# HW2.net
KiCad netlist of a schematic drawn in EAGLE
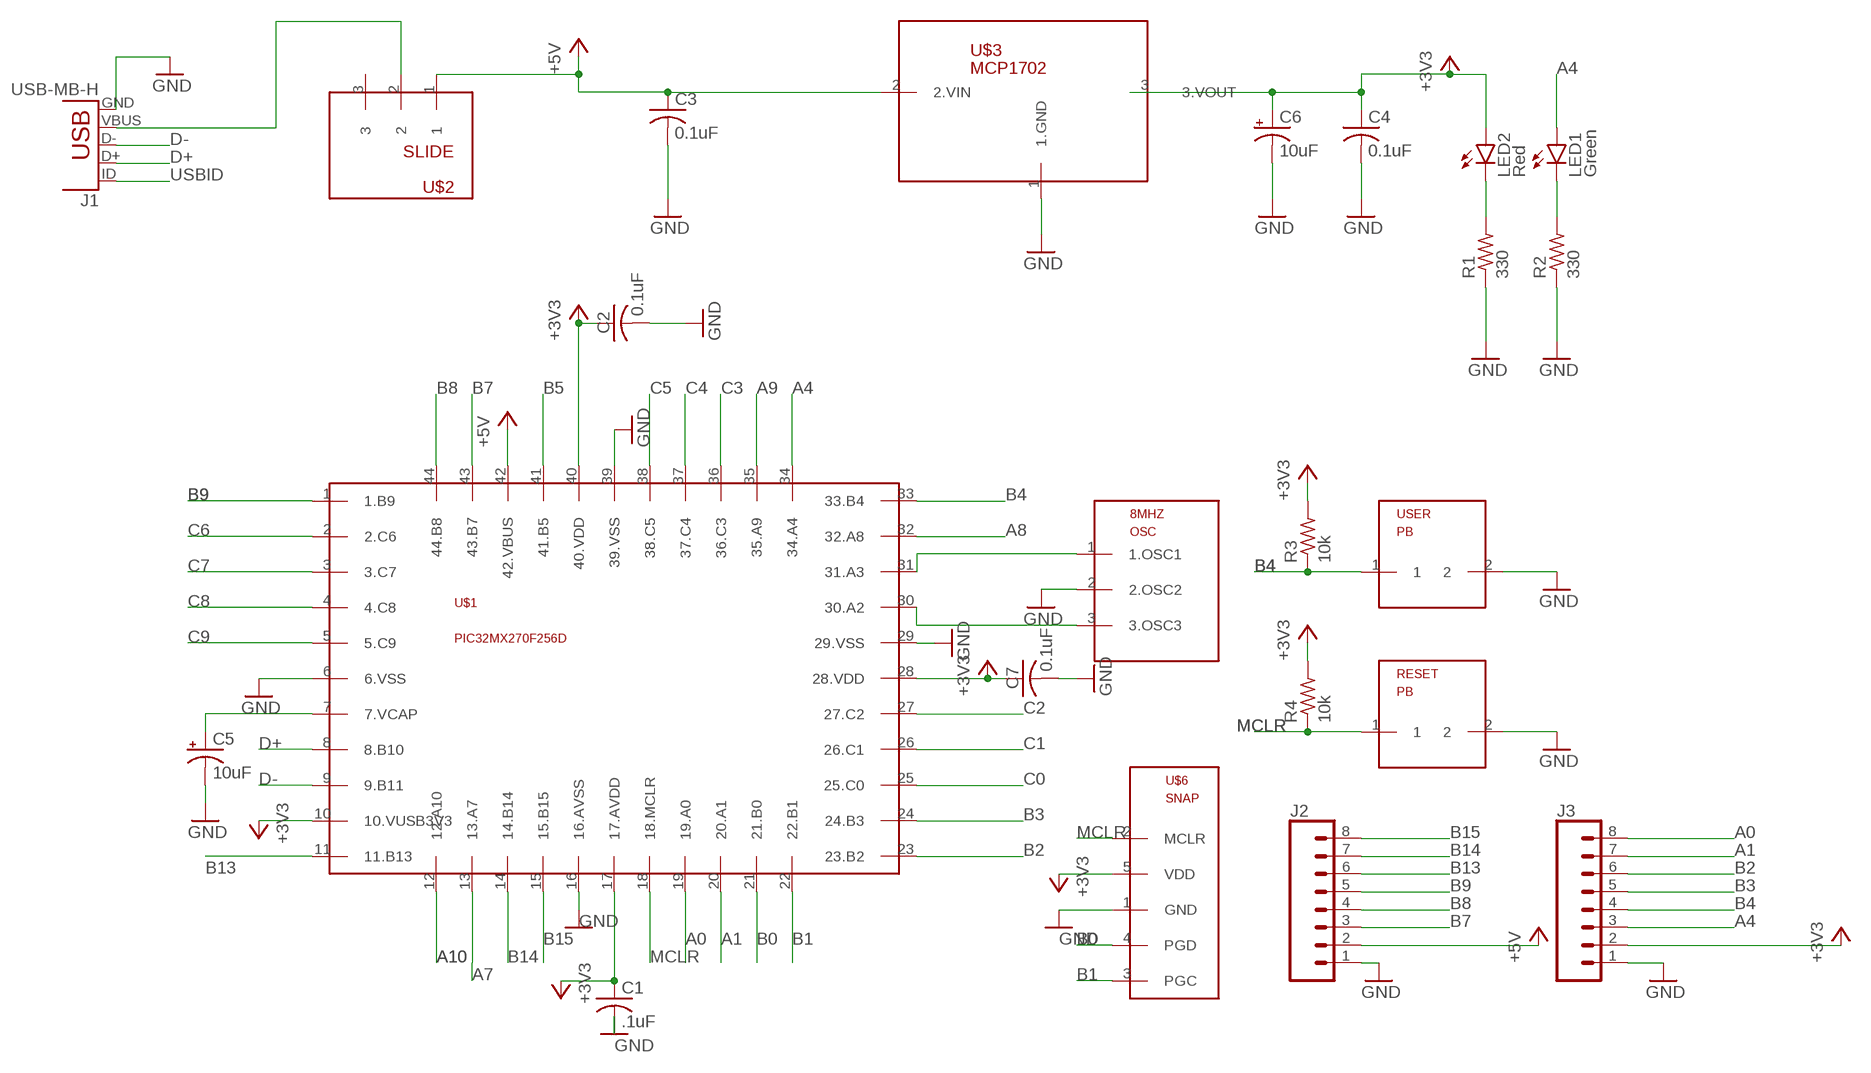
[diagram p0: schematic, sheet 1]

(export (version "E")
  (design (tool "Eeschema 10.0.6"))
  (components
    (comp (ref "8MHZ")
      (value "OSC")
      (footprint "eagle-import:OSC")
      (libsource (lib "eagle-import") (part "OSC"))
    )
    (comp (ref "C1")
      (value ".1uF")
      (footprint "eagle-import:C025-025X050")
      (libsource (lib "eagle-import") (part "C-US025-025X050"))
    )
    (comp (ref "C2")
      (value "0.1uF")
      (footprint "eagle-import:C025-025X050")
      (libsource (lib "eagle-import") (part "C-US025-025X050"))
    )
    (comp (ref "C3")
      (value "0.1uF")
      (footprint "eagle-import:C025-025X050")
      (libsource (lib "eagle-import") (part "C-US025-025X050"))
    )
    (comp (ref "C4")
      (value "0.1uF")
      (footprint "eagle-import:C025-025X050")
      (libsource (lib "eagle-import") (part "C-US025-025X050"))
    )
    (comp (ref "C5")
      (value "10uF")
      (footprint "eagle-import:B45181B")
      (libsource (lib "eagle-import") (part "CPOL-USB45181B"))
    )
    (comp (ref "C6")
      (value "10uF")
      (footprint "eagle-import:B45181B")
      (libsource (lib "eagle-import") (part "CPOL-USB45181B"))
    )
    (comp (ref "C7")
      (value "0.1uF")
      (footprint "eagle-import:C025-025X050")
      (libsource (lib "eagle-import") (part "C-US025-025X050"))
    )
    (comp (ref "J1")
      (value "USB-MB-H")
      (footprint "eagle-import:USB-MB-H")
      (libsource (lib "eagle-import") (part "USB-MB-H"))
    )
    (comp (ref "J2")
      (value "CONN_08")
      (footprint "eagle-import:CONN_08")
      (libsource (lib "eagle-import") (part "CONN_08"))
    )
    (comp (ref "J3")
      (value "CONN_08")
      (footprint "eagle-import:CONN_08")
      (libsource (lib "eagle-import") (part "CONN_08"))
    )
    (comp (ref "LED1")
      (value "Green")
      (footprint "eagle-import:LED3MM")
      (libsource (lib "eagle-import") (part "LED3MM"))
    )
    (comp (ref "LED2")
      (value "Red")
      (footprint "eagle-import:LED3MM")
      (libsource (lib "eagle-import") (part "LED3MM"))
    )
    (comp (ref "R1")
      (value "330")
      (footprint "eagle-import:0207_10")
      (libsource (lib "eagle-import") (part "R-US_0207/10"))
    )
    (comp (ref "R2")
      (value "330")
      (footprint "eagle-import:0207_10")
      (libsource (lib "eagle-import") (part "R-US_0207/10"))
    )
    (comp (ref "R3")
      (value "10k")
      (footprint "eagle-import:0207_10")
      (libsource (lib "eagle-import") (part "R-US_0207/10"))
    )
    (comp (ref "R4")
      (value "10k")
      (footprint "eagle-import:0207_10")
      (libsource (lib "eagle-import") (part "R-US_0207/10"))
    )
    (comp (ref "RESET")
      (value "PB")
      (footprint "eagle-import:PB")
      (libsource (lib "eagle-import") (part "PB"))
    )
    (comp (ref "U$1")
      (value "PIC32MX270F256D")
      (footprint "eagle-import:MQFP44-2")
      (libsource (lib "eagle-import") (part "PIC32MX270F256D"))
    )
    (comp (ref "U$2")
      (value "SLIDE")
      (footprint "eagle-import:SLIDE")
      (libsource (lib "eagle-import") (part "SLIDE"))
    )
    (comp (ref "U$3")
      (value "MCP1702")
      (footprint "eagle-import:TO92")
      (libsource (lib "eagle-import") (part "MCP1702"))
    )
    (comp (ref "U$6")
      (value "SNAP")
      (footprint "eagle-import:1X05")
      (libsource (lib "eagle-import") (part "SNAP"))
    )
    (comp (ref "USER")
      (value "PB")
      (footprint "eagle-import:PB")
      (libsource (lib "eagle-import") (part "PB"))
    )
  )
  (nets
    (net (code "1") (name "+3V3") (class "Default")
      (node (ref "C1") (pin "1") (pinfunction "1_1") (pintype "passive"))
      (node (ref "C2") (pin "1") (pinfunction "1_1") (pintype "passive"))
      (node (ref "C4") (pin "1") (pinfunction "1_1") (pintype "passive"))
      (node (ref "C6") (pin "+") (pinfunction "+_+") (pintype "passive"))
      (node (ref "C7") (pin "1") (pinfunction "1_1") (pintype "passive"))
      (node (ref "J3") (pin "2") (pinfunction "2_2") (pintype "passive"))
      (node (ref "LED2") (pin "A") (pinfunction "A_A") (pintype "passive"))
      (node (ref "R3") (pin "2") (pinfunction "2_2") (pintype "passive"))
      (node (ref "R4") (pin "2") (pinfunction "2_2") (pintype "passive"))
      (node (ref "U$1") (pin "10") (pinfunction "10.VUSB3V3_10") (pintype "bidirectional"))
      (node (ref "U$1") (pin "17") (pinfunction "17.AVDD_17") (pintype "bidirectional"))
      (node (ref "U$1") (pin "28") (pinfunction "28.VDD_28") (pintype "bidirectional"))
      (node (ref "U$1") (pin "40") (pinfunction "40.VDD_40") (pintype "bidirectional"))
      (node (ref "U$3") (pin "3") (pinfunction "3.VOUT_3") (pintype "bidirectional"))
      (node (ref "U$6") (pin "5") (pinfunction "VDD_5") (pintype "bidirectional"))
    )
    (net (code "2") (name "+5V") (class "Default")
      (node (ref "C3") (pin "1") (pinfunction "1_1") (pintype "passive"))
      (node (ref "J2") (pin "2") (pinfunction "2_2") (pintype "passive"))
      (node (ref "U$1") (pin "42") (pinfunction "42.VBUS_42") (pintype "bidirectional"))
      (node (ref "U$2") (pin "1") (pinfunction "1_1") (pintype "bidirectional"))
      (node (ref "U$3") (pin "2") (pinfunction "2.VIN_2") (pintype "bidirectional"))
    )
    (net (code "3") (name "/A0") (class "Default")
      (node (ref "J3") (pin "8") (pinfunction "8_8") (pintype "passive"))
      (node (ref "U$1") (pin "19") (pinfunction "19.A0_19") (pintype "bidirectional"))
    )
    (net (code "4") (name "/A1") (class "Default")
      (node (ref "J3") (pin "7") (pinfunction "7_7") (pintype "passive"))
      (node (ref "U$1") (pin "20") (pinfunction "20.A1_20") (pintype "bidirectional"))
    )
    (net (code "5") (name "/A4") (class "Default")
      (node (ref "J3") (pin "3") (pinfunction "3_3") (pintype "passive"))
      (node (ref "LED1") (pin "A") (pinfunction "A_A") (pintype "passive"))
      (node (ref "U$1") (pin "34") (pinfunction "34.A4_34") (pintype "bidirectional"))
    )
    (net (code "6") (name "/A7") (class "Default")
      (node (ref "U$1") (pin "13") (pinfunction "13.A7_13") (pintype "bidirectional"))
    )
    (net (code "7") (name "/A8") (class "Default")
      (node (ref "U$1") (pin "32") (pinfunction "32.A8_32") (pintype "bidirectional"))
    )
    (net (code "8") (name "/A9") (class "Default")
      (node (ref "U$1") (pin "35") (pinfunction "35.A9_35") (pintype "bidirectional"))
    )
    (net (code "9") (name "/A10") (class "Default")
      (node (ref "U$1") (pin "12") (pinfunction "12.A10_12") (pintype "bidirectional"))
    )
    (net (code "10") (name "/B0") (class "Default")
      (node (ref "U$1") (pin "21") (pinfunction "21.B0_21") (pintype "bidirectional"))
      (node (ref "U$6") (pin "4") (pinfunction "PGD_4") (pintype "bidirectional"))
    )
    (net (code "11") (name "/B1") (class "Default")
      (node (ref "U$1") (pin "22") (pinfunction "22.B1_22") (pintype "bidirectional"))
      (node (ref "U$6") (pin "3") (pinfunction "PGC_3") (pintype "bidirectional"))
    )
    (net (code "12") (name "/B2") (class "Default")
      (node (ref "J3") (pin "6") (pinfunction "6_6") (pintype "passive"))
      (node (ref "U$1") (pin "23") (pinfunction "23.B2_23") (pintype "bidirectional"))
    )
    (net (code "13") (name "/B3") (class "Default")
      (node (ref "J3") (pin "5") (pinfunction "5_5") (pintype "passive"))
      (node (ref "U$1") (pin "24") (pinfunction "24.B3_24") (pintype "bidirectional"))
    )
    (net (code "14") (name "/B4") (class "Default")
      (node (ref "J3") (pin "4") (pinfunction "4_4") (pintype "passive"))
      (node (ref "R3") (pin "1") (pinfunction "1_1") (pintype "passive"))
      (node (ref "U$1") (pin "33") (pinfunction "33.B4_33") (pintype "bidirectional"))
      (node (ref "USER") (pin "1") (pinfunction "1_1") (pintype "bidirectional"))
    )
    (net (code "15") (name "/B5") (class "Default")
      (node (ref "U$1") (pin "41") (pinfunction "41.B5_41") (pintype "bidirectional"))
    )
    (net (code "16") (name "/B7") (class "Default")
      (node (ref "J2") (pin "3") (pinfunction "3_3") (pintype "passive"))
      (node (ref "U$1") (pin "43") (pinfunction "43.B7_43") (pintype "bidirectional"))
    )
    (net (code "17") (name "/B8") (class "Default")
      (node (ref "J2") (pin "4") (pinfunction "4_4") (pintype "passive"))
      (node (ref "U$1") (pin "44") (pinfunction "44.B8_44") (pintype "bidirectional"))
    )
    (net (code "18") (name "/B9") (class "Default")
      (node (ref "J2") (pin "5") (pinfunction "5_5") (pintype "passive"))
      (node (ref "U$1") (pin "1") (pinfunction "1.B9_1") (pintype "bidirectional"))
    )
    (net (code "19") (name "/B13") (class "Default")
      (node (ref "J2") (pin "6") (pinfunction "6_6") (pintype "passive"))
      (node (ref "U$1") (pin "11") (pinfunction "11.B13_11") (pintype "bidirectional"))
    )
    (net (code "20") (name "/B14") (class "Default")
      (node (ref "J2") (pin "7") (pinfunction "7_7") (pintype "passive"))
      (node (ref "U$1") (pin "14") (pinfunction "14.B14_14") (pintype "bidirectional"))
    )
    (net (code "21") (name "/B15") (class "Default")
      (node (ref "J2") (pin "8") (pinfunction "8_8") (pintype "passive"))
      (node (ref "U$1") (pin "15") (pinfunction "15.B15_15") (pintype "bidirectional"))
    )
    (net (code "22") (name "/C0") (class "Default")
      (node (ref "U$1") (pin "25") (pinfunction "25.C0_25") (pintype "bidirectional"))
    )
    (net (code "23") (name "/C1") (class "Default")
      (node (ref "U$1") (pin "26") (pinfunction "26.C1_26") (pintype "bidirectional"))
    )
    (net (code "24") (name "/C2") (class "Default")
      (node (ref "U$1") (pin "27") (pinfunction "27.C2_27") (pintype "bidirectional"))
    )
    (net (code "25") (name "/C3") (class "Default")
      (node (ref "U$1") (pin "36") (pinfunction "36.C3_36") (pintype "bidirectional"))
    )
    (net (code "26") (name "/C4") (class "Default")
      (node (ref "U$1") (pin "37") (pinfunction "37.C4_37") (pintype "bidirectional"))
    )
    (net (code "27") (name "/C5") (class "Default")
      (node (ref "U$1") (pin "38") (pinfunction "38.C5_38") (pintype "bidirectional"))
    )
    (net (code "28") (name "/C6") (class "Default")
      (node (ref "U$1") (pin "2") (pinfunction "2.C6_2") (pintype "bidirectional"))
    )
    (net (code "29") (name "/C7") (class "Default")
      (node (ref "U$1") (pin "3") (pinfunction "3.C7_3") (pintype "bidirectional"))
    )
    (net (code "30") (name "/C8") (class "Default")
      (node (ref "U$1") (pin "4") (pinfunction "4.C8_4") (pintype "bidirectional"))
    )
    (net (code "31") (name "/C9") (class "Default")
      (node (ref "U$1") (pin "5") (pinfunction "5.C9_5") (pintype "bidirectional"))
    )
    (net (code "32") (name "/D+") (class "Default")
      (node (ref "J1") (pin "D+") (pinfunction "D+_D+") (pintype "bidirectional"))
      (node (ref "U$1") (pin "8") (pinfunction "8.B10_8") (pintype "bidirectional"))
    )
    (net (code "33") (name "/D-") (class "Default")
      (node (ref "J1") (pin "D-") (pinfunction "D-_D-") (pintype "bidirectional"))
      (node (ref "U$1") (pin "9") (pinfunction "9.B11_9") (pintype "bidirectional"))
    )
    (net (code "34") (name "/MCLR") (class "Default")
      (node (ref "R4") (pin "1") (pinfunction "1_1") (pintype "passive"))
      (node (ref "RESET") (pin "1") (pinfunction "1_1") (pintype "bidirectional"))
      (node (ref "U$1") (pin "18") (pinfunction "18.MCLR_18") (pintype "bidirectional"))
      (node (ref "U$6") (pin "2") (pinfunction "MCLR_2") (pintype "bidirectional"))
    )
    (net (code "35") (name "/USBID") (class "Default")
      (node (ref "J1") (pin "ID") (pinfunction "ID_ID") (pintype "bidirectional"))
    )
    (net (code "36") (name "GND") (class "Default")
      (node (ref "8MHZ") (pin "2") (pinfunction "2.OSC2_2") (pintype "bidirectional"))
      (node (ref "C1") (pin "2") (pinfunction "2_2") (pintype "passive"))
      (node (ref "C2") (pin "2") (pinfunction "2_2") (pintype "passive"))
      (node (ref "C3") (pin "2") (pinfunction "2_2") (pintype "passive"))
      (node (ref "C4") (pin "2") (pinfunction "2_2") (pintype "passive"))
      (node (ref "C5") (pin "-") (pinfunction "-_-") (pintype "passive"))
      (node (ref "C6") (pin "-") (pinfunction "-_-") (pintype "passive"))
      (node (ref "C7") (pin "2") (pinfunction "2_2") (pintype "passive"))
      (node (ref "J1") (pin "GND") (pinfunction "GND_GND") (pintype "bidirectional"))
      (node (ref "J2") (pin "1") (pinfunction "1_1") (pintype "passive"))
      (node (ref "J3") (pin "1") (pinfunction "1_1") (pintype "passive"))
      (node (ref "R1") (pin "1") (pinfunction "1_1") (pintype "passive"))
      (node (ref "R2") (pin "1") (pinfunction "1_1") (pintype "passive"))
      (node (ref "RESET") (pin "2") (pinfunction "2_2") (pintype "bidirectional"))
      (node (ref "U$1") (pin "16") (pinfunction "16.AVSS_16") (pintype "bidirectional"))
      (node (ref "U$1") (pin "29") (pinfunction "29.VSS_29") (pintype "bidirectional"))
      (node (ref "U$1") (pin "39") (pinfunction "39.VSS_39") (pintype "bidirectional"))
      (node (ref "U$1") (pin "6") (pinfunction "6.VSS_6") (pintype "bidirectional"))
      (node (ref "U$3") (pin "1") (pinfunction "1.GND_1") (pintype "bidirectional"))
      (node (ref "U$6") (pin "1") (pinfunction "GND_1") (pintype "bidirectional"))
      (node (ref "USER") (pin "2") (pinfunction "2_2") (pintype "bidirectional"))
    )
    (net (code "37") (name "Net-(8MHZ-1.OSC1)") (class "Default")
      (node (ref "8MHZ") (pin "1") (pinfunction "1.OSC1_1") (pintype "bidirectional"))
      (node (ref "U$1") (pin "31") (pinfunction "31.A3_31") (pintype "bidirectional"))
    )
    (net (code "38") (name "Net-(8MHZ-3.OSC3)") (class "Default")
      (node (ref "8MHZ") (pin "3") (pinfunction "3.OSC3_3") (pintype "bidirectional"))
      (node (ref "U$1") (pin "30") (pinfunction "30.A2_30") (pintype "bidirectional"))
    )
    (net (code "39") (name "Net-(J1-PadVBUS)") (class "Default")
      (node (ref "J1") (pin "VBUS") (pinfunction "VBUS_VBUS") (pintype "bidirectional"))
      (node (ref "U$2") (pin "2") (pinfunction "2_2") (pintype "bidirectional"))
    )
    (net (code "40") (name "Net-(LED1-C)") (class "Default")
      (node (ref "LED1") (pin "K") (pinfunction "C_K") (pintype "passive"))
      (node (ref "R2") (pin "2") (pinfunction "2_2") (pintype "passive"))
    )
    (net (code "41") (name "Net-(LED2-C)") (class "Default")
      (node (ref "LED2") (pin "K") (pinfunction "C_K") (pintype "passive"))
      (node (ref "R1") (pin "2") (pinfunction "2_2") (pintype "passive"))
    )
    (net (code "42") (name "Net-(U$1-7.VCAP)") (class "Default")
      (node (ref "C5") (pin "+") (pinfunction "+_+") (pintype "passive"))
      (node (ref "U$1") (pin "7") (pinfunction "7.VCAP_7") (pintype "bidirectional"))
    )
    (net (code "43") (name "unconnected-(U$2-Pad3)") (class "Default")
      (node (ref "U$2") (pin "3") (pinfunction "3_3") (pintype "bidirectional"))
    )
  )
)
